# battery.net
KiCad netlist of a schematic drawn in Altium Designer
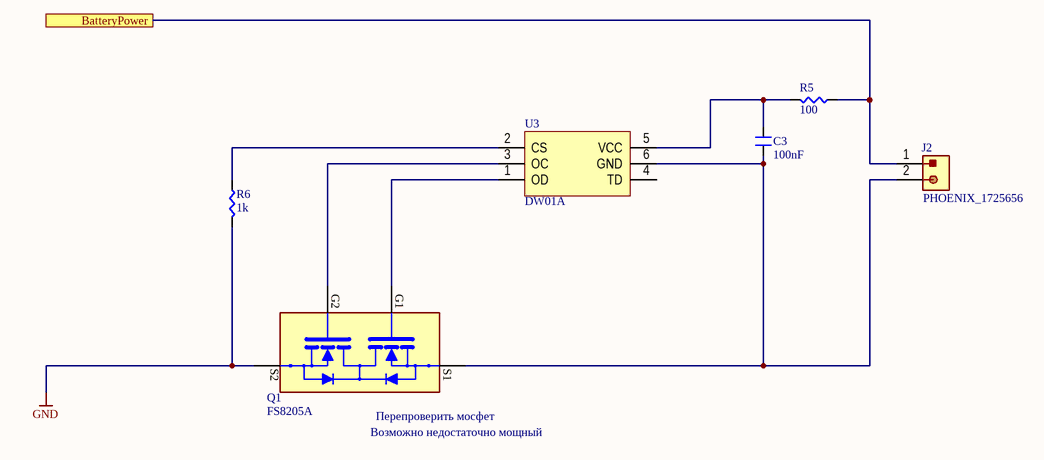
[diagram p0: battery.SchDoc]

(export (version "E")
  (design (tool "Eeschema 10.0.6"))
  (components
    (comp (ref "C3")
      (value "100nF")
      (footprint "CAP0603")
      (description "Tolerance ±10%\nRated Voltage 50Vdc\nTemperature 0±30ppm/℃")
      (fields (field (name "PART NUMBER") "GCM188R71H104KA57J") (field (name "TOLERANCE") "10%"))
      (libsource (lib "Lib_Kam") (part "Capacitor"))
    )
    (comp (ref "J2")
      (value "PHOENIX_1725656")
      (footprint "PHOENIX_1725656")
      (description "Fixed Terminal Blocks 2P 2.54mm 90DEG")
      (fields (field (name "PART NUMBER") "1725656") (field (name "MANUFACTURER") "Phoenix Contact"))
      (libsource (lib "Lib_Kam") (part "PHOENIX_1725656"))
    )
    (comp (ref "Q1")
      (value "FS8205A")
      (footprint "TSSOP-8_MOSFET")
      (description "Dual N-Channel Enhancement Mode Power MOSFET")
      (fields (field (name "MANUFACTURER") "Fortune Semiconductor"))
      (libsource (lib "Lib_Kam") (part "Array_2_N-Channel"))
    )
    (comp (ref "R5")
      (value "100")
      (footprint "RES0603")
      (description "Tolerance ±1%\nPower (Watts) 0.1W, 1/10W\nTemperature Coefficient ±100ppm/°C")
      (fields (field (name "PART NUMBER") "652-CR0603AFX1000ELF") (field (name "TOLERANCE") "0.01"))
      (libsource (lib "Lib_Kam") (part "Resistor"))
    )
    (comp (ref "R6")
      (value "1k")
      (footprint "RES0603")
      (description "Tolerance ±1%\nPower (Watts) 0.1W, 1/10W\nTemperature Coefficient ±25ppm/°C")
      (fields (field (name "PART NUMBER") "CRT0603-FY-1001ELF") (field (name "TOLERANCE") "0.01"))
      (libsource (lib "Lib_Kam") (part "Resistor"))
    )
    (comp (ref "U3")
      (value "DW01A")
      (footprint "SOT-23-6")
      (description "Battery Management Battery Protection IC")
      (fields (field (name "MANUFACTURER") "H&M Semiconductor"))
      (libsource (lib "Lib_Kam") (part "DW01A"))
    )
  )
  (nets
    (net (code "1") (name "/BatteryPower") (class "Default")
      (node (ref "J2") (pin "1") (pinfunction "1_1") (pintype "passive"))
      (node (ref "R5") (pin "2") (pintype "passive"))
    )
    (net (code "2") (name "GND") (class "Default")
      (node (ref "Q1") (pin "S2") (pinfunction "S2_S2") (pintype "passive"))
      (node (ref "R6") (pin "1") (pintype "passive"))
    )
    (net (code "3") (name "Net-(U3-CS)") (class "Default")
      (node (ref "R6") (pin "2") (pintype "passive"))
      (node (ref "U3") (pin "2") (pinfunction "CS_2") (pintype "passive"))
    )
    (net (code "4") (name "Net-(U3-GND)") (class "Default")
      (node (ref "C3") (pin "1") (pinfunction "2_1") (pintype "passive"))
      (node (ref "J2") (pin "2") (pinfunction "2_2") (pintype "passive"))
      (node (ref "Q1") (pin "S1") (pinfunction "S1_S1") (pintype "passive"))
      (node (ref "U3") (pin "6") (pinfunction "GND_6") (pintype "passive"))
    )
    (net (code "5") (name "Net-(U3-OC)") (class "Default")
      (node (ref "Q1") (pin "G2") (pinfunction "G2_G2") (pintype "passive"))
      (node (ref "U3") (pin "3") (pinfunction "OC_3") (pintype "passive"))
    )
    (net (code "6") (name "Net-(U3-OD)") (class "Default")
      (node (ref "Q1") (pin "G1") (pinfunction "G1_G1") (pintype "passive"))
      (node (ref "U3") (pin "1") (pinfunction "OD_1") (pintype "passive"))
    )
    (net (code "7") (name "Net-(U3-VCC)") (class "Default")
      (node (ref "C3") (pin "2") (pinfunction "2_2") (pintype "passive"))
      (node (ref "R5") (pin "1") (pintype "passive"))
      (node (ref "U3") (pin "5") (pinfunction "VCC_5") (pintype "passive"))
    )
    (net (code "8") (name "unconnected-(U3-TD-Pad4)") (class "Default")
      (node (ref "U3") (pin "4") (pinfunction "TD_4") (pintype "passive"))
    )
  )
)
